# Projeto_Lora.net
KiCad netlist of a schematic drawn in EAGLE
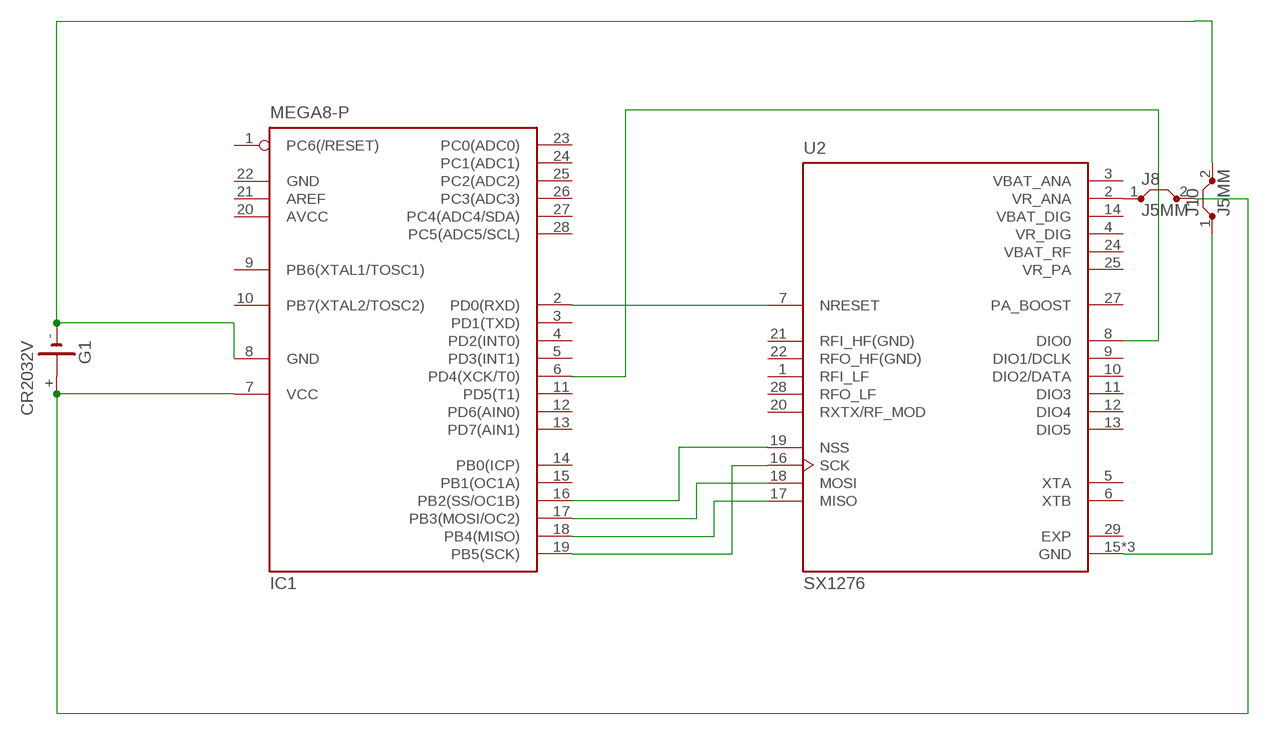
[diagram p0: schematic, sheet 1]

(export (version "E")
  (design (tool "Eeschema 10.0.6"))
  (components
    (comp (ref "G1")
      (value "CR2032V")
      (footprint "eagle-import:CR2032V")
      (libsource (lib "eagle-import") (part "CR2032V"))
    )
    (comp (ref "IC1")
      (value "MEGA8-P")
      (footprint "eagle-import:DIL28-3")
      (libsource (lib "eagle-import") (part "MEGA8-P"))
    )
    (comp (ref "J8")
      (value "J5MM")
      (footprint "eagle-import:05")
      (libsource (lib "eagle-import") (part "J5MM"))
    )
    (comp (ref "J10")
      (value "J5MM")
      (footprint "eagle-import:05")
      (libsource (lib "eagle-import") (part "J5MM"))
    )
    (comp (ref "U2")
      (value "SX1276")
      (footprint "eagle-import:QFN65P600X600X100-29N")
      (fields (field (name "MF") "Semtech Corporation"))
      (libsource (lib "eagle-import") (part "SX1276"))
    )
  )
  (nets
    (net (code "1") (name "/AVCC") (class "Default")
      (node (ref "IC1") (pin "20") (pinfunction "AVCC_20") (pintype "power_in"))
    )
    (net (code "2") (name "/EXP") (class "Default")
      (node (ref "U2") (pin "29") (pinfunction "EXP_29") (pintype "power_in"))
    )
    (net (code "3") (name "/GND") (class "Default")
      (node (ref "IC1") (pin "22") (pinfunction "GND_22") (pintype "power_in"))
    )
    (net (code "4") (name "/VBAT_ANA") (class "Default")
      (node (ref "U2") (pin "3") (pinfunction "VBAT_ANA_3") (pintype "power_in"))
    )
    (net (code "5") (name "/VBAT_DIG") (class "Default")
      (node (ref "U2") (pin "14") (pinfunction "VBAT_DIG_14") (pintype "power_in"))
    )
    (net (code "6") (name "/VBAT_RF") (class "Default")
      (node (ref "U2") (pin "24") (pinfunction "VBAT_RF_24") (pintype "power_in"))
    )
    (net (code "7") (name "/VR_DIG") (class "Default")
      (node (ref "U2") (pin "4") (pinfunction "VR_DIG_4") (pintype "power_in"))
    )
    (net (code "8") (name "/VR_PA") (class "Default")
      (node (ref "U2") (pin "25") (pinfunction "VR_PA_25") (pintype "power_in"))
    )
    (net (code "9") (name "Net-(G1-Pad-)") (class "Default")
      (node (ref "G1") (pin "-") (pinfunction "-_-") (pintype "passive"))
      (node (ref "IC1") (pin "8") (pinfunction "GND_8") (pintype "power_in"))
      (node (ref "J10") (pin "2") (pinfunction "2_2") (pintype "passive"))
    )
    (net (code "10") (name "Net-(IC1-PB2(SS{slash}OC1B))") (class "Default")
      (node (ref "IC1") (pin "16") (pinfunction "PB2(SS/OC1B)_16") (pintype "bidirectional"))
      (node (ref "U2") (pin "19") (pinfunction "NSS_19") (pintype "input"))
    )
    (net (code "11") (name "Net-(IC1-PB3(MOSI{slash}OC2))") (class "Default")
      (node (ref "IC1") (pin "17") (pinfunction "PB3(MOSI/OC2)_17") (pintype "bidirectional"))
      (node (ref "U2") (pin "18") (pinfunction "MOSI_18") (pintype "input"))
    )
    (net (code "12") (name "Net-(IC1-PB4(MISO))") (class "Default")
      (node (ref "IC1") (pin "18") (pinfunction "PB4(MISO)_18") (pintype "bidirectional"))
      (node (ref "U2") (pin "17") (pinfunction "MISO_17") (pintype "output"))
    )
    (net (code "13") (name "Net-(IC1-PB5(SCK))") (class "Default")
      (node (ref "IC1") (pin "19") (pinfunction "PB5(SCK)_19") (pintype "bidirectional"))
      (node (ref "U2") (pin "16") (pinfunction "SCK_16") (pintype "input"))
    )
    (net (code "14") (name "Net-(IC1-PD0(RXD))") (class "Default")
      (node (ref "IC1") (pin "2") (pinfunction "PD0(RXD)_2") (pintype "bidirectional"))
      (node (ref "U2") (pin "7") (pinfunction "NRESET_7") (pintype "bidirectional"))
    )
    (net (code "15") (name "Net-(IC1-PD4(XCK{slash}T0))") (class "Default")
      (node (ref "IC1") (pin "6") (pinfunction "PD4(XCK/T0)_6") (pintype "bidirectional"))
      (node (ref "U2") (pin "8") (pinfunction "DIO0_8") (pintype "bidirectional"))
    )
    (net (code "16") (name "Net-(IC1-VCC)") (class "Default")
      (node (ref "G1") (pin "+") (pinfunction "+_+") (pintype "passive"))
      (node (ref "IC1") (pin "7") (pinfunction "VCC_7") (pintype "power_in"))
      (node (ref "J8") (pin "2") (pinfunction "2_2") (pintype "passive"))
    )
    (net (code "17") (name "Net-(J10-Pad1)") (class "Default")
      (node (ref "J10") (pin "1") (pinfunction "1_1") (pintype "passive"))
      (node (ref "U2") (pin "15") (pinfunction "GND_15") (pintype "power_in"))
      (node (ref "U2") (pin "23") (pinfunction "GND_23") (pintype "power_in"))
      (node (ref "U2") (pin "26") (pinfunction "GND_26") (pintype "power_in"))
    )
    (net (code "18") (name "Net-(U2-VR_ANA)") (class "Default")
      (node (ref "J8") (pin "1") (pinfunction "1_1") (pintype "passive"))
      (node (ref "U2") (pin "2") (pinfunction "VR_ANA_2") (pintype "power_in"))
    )
    (net (code "19") (name "unconnected-(G1-+-Pad+@1)") (class "Default")
      (node (ref "G1") (pin "+@1") (pinfunction "+_+@1") (pintype "passive"))
    )
    (net (code "20") (name "unconnected-(IC1-AREF-Pad21)") (class "Default")
      (node (ref "IC1") (pin "21") (pinfunction "AREF_21") (pintype "passive"))
    )
    (net (code "21") (name "unconnected-(IC1-PB0(ICP)-Pad14)") (class "Default")
      (node (ref "IC1") (pin "14") (pinfunction "PB0(ICP)_14") (pintype "bidirectional"))
    )
    (net (code "22") (name "unconnected-(IC1-PB1(OC1A)-Pad15)") (class "Default")
      (node (ref "IC1") (pin "15") (pinfunction "PB1(OC1A)_15") (pintype "bidirectional"))
    )
    (net (code "23") (name "unconnected-(IC1-PB6(XTAL1{slash}TOSC1)-Pad9)") (class "Default")
      (node (ref "IC1") (pin "9") (pinfunction "PB6(XTAL1/TOSC1)_9") (pintype "bidirectional"))
    )
    (net (code "24") (name "unconnected-(IC1-PB7(XTAL2{slash}TOSC2)-Pad10)") (class "Default")
      (node (ref "IC1") (pin "10") (pinfunction "PB7(XTAL2/TOSC2)_10") (pintype "bidirectional"))
    )
    (net (code "25") (name "unconnected-(IC1-PC0(ADC0)-Pad23)") (class "Default")
      (node (ref "IC1") (pin "23") (pinfunction "PC0(ADC0)_23") (pintype "bidirectional"))
    )
    (net (code "26") (name "unconnected-(IC1-PC1(ADC1)-Pad24)") (class "Default")
      (node (ref "IC1") (pin "24") (pinfunction "PC1(ADC1)_24") (pintype "bidirectional"))
    )
    (net (code "27") (name "unconnected-(IC1-PC2(ADC2)-Pad25)") (class "Default")
      (node (ref "IC1") (pin "25") (pinfunction "PC2(ADC2)_25") (pintype "bidirectional"))
    )
    (net (code "28") (name "unconnected-(IC1-PC3(ADC3)-Pad26)") (class "Default")
      (node (ref "IC1") (pin "26") (pinfunction "PC3(ADC3)_26") (pintype "bidirectional"))
    )
    (net (code "29") (name "unconnected-(IC1-PC4(ADC4{slash}SDA)-Pad27)") (class "Default")
      (node (ref "IC1") (pin "27") (pinfunction "PC4(ADC4/SDA)_27") (pintype "bidirectional"))
    )
    (net (code "30") (name "unconnected-(IC1-PC5(ADC5{slash}SCL)-Pad28)") (class "Default")
      (node (ref "IC1") (pin "28") (pinfunction "PC5(ADC5/SCL)_28") (pintype "bidirectional"))
    )
    (net (code "31") (name "unconnected-(IC1-PC6({slash}RESET)-Pad1)") (class "Default")
      (node (ref "IC1") (pin "1") (pinfunction "PC6(/RESET)_1") (pintype "bidirectional"))
    )
    (net (code "32") (name "unconnected-(IC1-PD1(TXD)-Pad3)") (class "Default")
      (node (ref "IC1") (pin "3") (pinfunction "PD1(TXD)_3") (pintype "bidirectional"))
    )
    (net (code "33") (name "unconnected-(IC1-PD2(INT0)-Pad4)") (class "Default")
      (node (ref "IC1") (pin "4") (pinfunction "PD2(INT0)_4") (pintype "bidirectional"))
    )
    (net (code "34") (name "unconnected-(IC1-PD3(INT1)-Pad5)") (class "Default")
      (node (ref "IC1") (pin "5") (pinfunction "PD3(INT1)_5") (pintype "bidirectional"))
    )
    (net (code "35") (name "unconnected-(IC1-PD5(T1)-Pad11)") (class "Default")
      (node (ref "IC1") (pin "11") (pinfunction "PD5(T1)_11") (pintype "bidirectional"))
    )
    (net (code "36") (name "unconnected-(IC1-PD6(AIN0)-Pad12)") (class "Default")
      (node (ref "IC1") (pin "12") (pinfunction "PD6(AIN0)_12") (pintype "bidirectional"))
    )
    (net (code "37") (name "unconnected-(IC1-PD7(AIN1)-Pad13)") (class "Default")
      (node (ref "IC1") (pin "13") (pinfunction "PD7(AIN1)_13") (pintype "bidirectional"))
    )
    (net (code "38") (name "unconnected-(U2-DIO1{slash}DCLK-Pad9)") (class "Default")
      (node (ref "U2") (pin "9") (pinfunction "DIO1/DCLK_9") (pintype "bidirectional"))
    )
    (net (code "39") (name "unconnected-(U2-DIO2{slash}DATA-Pad10)") (class "Default")
      (node (ref "U2") (pin "10") (pinfunction "DIO2/DATA_10") (pintype "bidirectional"))
    )
    (net (code "40") (name "unconnected-(U2-DIO3-Pad11)") (class "Default")
      (node (ref "U2") (pin "11") (pinfunction "DIO3_11") (pintype "bidirectional"))
    )
    (net (code "41") (name "unconnected-(U2-DIO4-Pad12)") (class "Default")
      (node (ref "U2") (pin "12") (pinfunction "DIO4_12") (pintype "bidirectional"))
    )
    (net (code "42") (name "unconnected-(U2-DIO5-Pad13)") (class "Default")
      (node (ref "U2") (pin "13") (pinfunction "DIO5_13") (pintype "bidirectional"))
    )
    (net (code "43") (name "unconnected-(U2-PA_BOOST-Pad27)") (class "Default")
      (node (ref "U2") (pin "27") (pinfunction "PA_BOOST_27") (pintype "output"))
    )
    (net (code "44") (name "unconnected-(U2-RFI_HF(GND)-Pad21)") (class "Default")
      (node (ref "U2") (pin "21") (pinfunction "RFI_HF(GND)_21") (pintype "input"))
    )
    (net (code "45") (name "unconnected-(U2-RFI_LF-Pad1)") (class "Default")
      (node (ref "U2") (pin "1") (pinfunction "RFI_LF_1") (pintype "input"))
    )
    (net (code "46") (name "unconnected-(U2-RFO_HF(GND)-Pad22)") (class "Default")
      (node (ref "U2") (pin "22") (pinfunction "RFO_HF(GND)_22") (pintype "output"))
    )
    (net (code "47") (name "unconnected-(U2-RFO_LF-Pad28)") (class "Default")
      (node (ref "U2") (pin "28") (pinfunction "RFO_LF_28") (pintype "output"))
    )
    (net (code "48") (name "unconnected-(U2-RXTX{slash}RF_MOD-Pad20)") (class "Default")
      (node (ref "U2") (pin "20") (pinfunction "RXTX/RF_MOD_20") (pintype "output"))
    )
    (net (code "49") (name "unconnected-(U2-XTA-Pad5)") (class "Default")
      (node (ref "U2") (pin "5") (pinfunction "XTA_5") (pintype "bidirectional"))
    )
    (net (code "50") (name "unconnected-(U2-XTB-Pad6)") (class "Default")
      (node (ref "U2") (pin "6") (pinfunction "XTB_6") (pintype "bidirectional"))
    )
  )
)
